# QSPI_Flash_eMMC_uSD-Card.net
KiCad netlist of a schematic drawn in Altium Designer
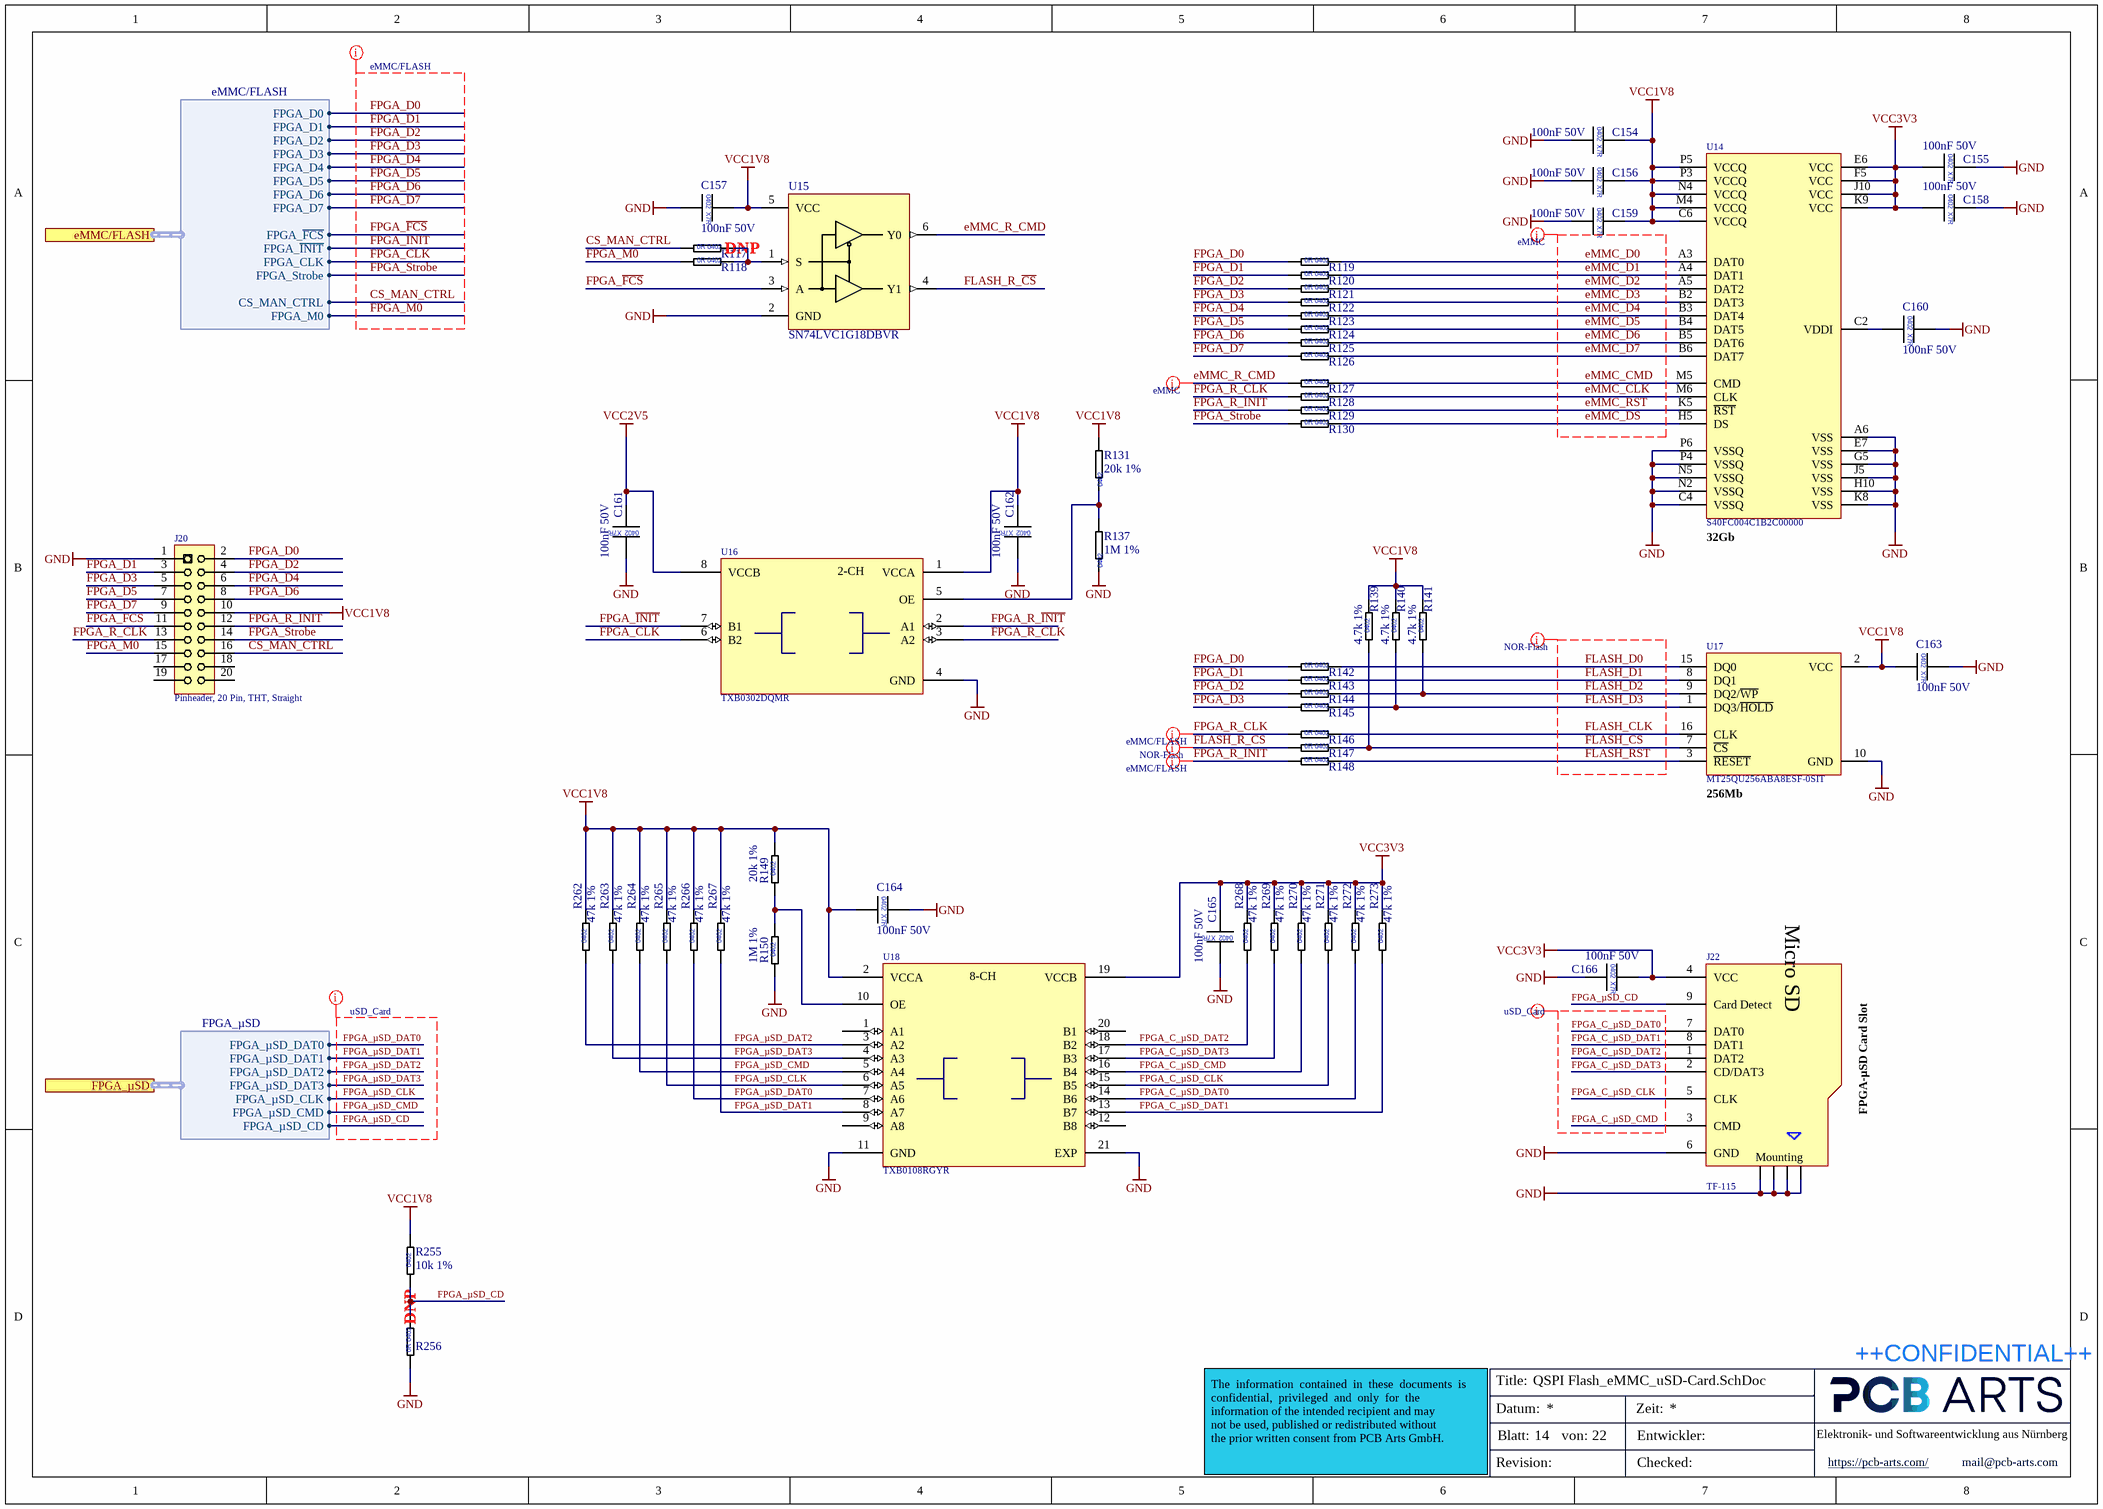
[diagram p0: QSPI Flash_eMMC_uSD-Card.SchDoc]

(export (version "E")
  (design (tool "Eeschema 10.0.6"))
  (components
    (comp (ref "C154")
      (value "100nF 50V")
      (footprint "Cap:CAP_0402_L")
      (description "Multilayer Ceramic Capacitors MLCC - SMD/SMT 0402 50VDC")
      (libsource (lib "Cap") (part "CAP_0402_100nF_50V"))
    )
    (comp (ref "C155")
      (value "100nF 50V")
      (footprint "Cap:CAP_0402_L")
      (description "Multilayer Ceramic Capacitors MLCC - SMD/SMT 0402 50VDC")
      (libsource (lib "Cap") (part "CAP_0402_100nF_50V"))
    )
    (comp (ref "C156")
      (value "100nF 50V")
      (footprint "Cap:CAP_0402_L")
      (description "Multilayer Ceramic Capacitors MLCC - SMD/SMT 0402 50VDC")
      (libsource (lib "Cap") (part "CAP_0402_100nF_50V"))
    )
    (comp (ref "C157")
      (value "100nF 50V")
      (footprint "Cap:CAP_0402_L")
      (description "Multilayer Ceramic Capacitors MLCC - SMD/SMT 0402 50VDC")
      (libsource (lib "Cap") (part "CAP_0402_100nF_50V"))
    )
    (comp (ref "C158")
      (value "100nF 50V")
      (footprint "Cap:CAP_0402_L")
      (description "Multilayer Ceramic Capacitors MLCC - SMD/SMT 0402 50VDC")
      (libsource (lib "Cap") (part "CAP_0402_100nF_50V"))
    )
    (comp (ref "C159")
      (value "100nF 50V")
      (footprint "Cap:CAP_0402_L")
      (description "Multilayer Ceramic Capacitors MLCC - SMD/SMT 0402 50VDC")
      (libsource (lib "Cap") (part "CAP_0402_100nF_50V"))
    )
    (comp (ref "C160")
      (value "100nF 50V")
      (footprint "Cap:CAP_0402_L")
      (description "Multilayer Ceramic Capacitors MLCC - SMD/SMT 0402 50VDC")
      (libsource (lib "Cap") (part "CAP_0402_100nF_50V"))
    )
    (comp (ref "C161")
      (value "100nF 50V")
      (footprint "Cap:CAP_0402_L")
      (description "Multilayer Ceramic Capacitors MLCC - SMD/SMT 0402 50VDC")
      (libsource (lib "") (part "CAP_0402_100nF_50V_1"))
    )
    (comp (ref "C162")
      (value "100nF 50V")
      (footprint "Cap:CAP_0402_L")
      (description "Multilayer Ceramic Capacitors MLCC - SMD/SMT 0402 50VDC")
      (libsource (lib "") (part "CAP_0402_100nF_50V_1"))
    )
    (comp (ref "C163")
      (value "100nF 50V")
      (footprint "Cap:CAP_0402_L")
      (description "Multilayer Ceramic Capacitors MLCC - SMD/SMT 0402 50VDC")
      (libsource (lib "Cap") (part "CAP_0402_100nF_50V"))
    )
    (comp (ref "C164")
      (value "100nF 50V")
      (footprint "Cap:CAP_0402_L")
      (description "Multilayer Ceramic Capacitors MLCC - SMD/SMT 0402 50VDC")
      (libsource (lib "Cap") (part "CAP_0402_100nF_50V"))
    )
    (comp (ref "C165")
      (value "100nF 50V")
      (footprint "Cap:CAP_0402_L")
      (description "Multilayer Ceramic Capacitors MLCC - SMD/SMT 0402 50VDC")
      (libsource (lib "") (part "CAP_0402_100nF_50V_1"))
    )
    (comp (ref "C166")
      (value "100nF 50V")
      (footprint "Cap:CAP_0402_L")
      (description "Multilayer Ceramic Capacitors MLCC - SMD/SMT 0402 50VDC")
      (libsource (lib "Cap") (part "CAP_0402_100nF_50V"))
    )
    (comp (ref "J20")
      (value "Pinheader, 20 Pin, THT, Straight")
      (footprint "Conn:62702021621")
      (description "Box Pin header THT 1.27mm 20Pol Straight")
      (libsource (lib "Conn") (part "62702021621_Box Pin header THT 1.27mm 20Pol Straight"))
    )
    (comp (ref "J22")
      (value "TF-115")
      (footprint "conn:TF-115")
      (description "microSD™ Memory Card 8 connector&Ejector 14.5x14.75x1.85mm Card Sockets Connector")
      (libsource (lib "Conn") (part "TF-115_microSD™ Memory Card 8 connector"))
    )
    (comp (ref "R117")
      (value "0R Jumper")
      (footprint "Res:RES_0402_L")
      (description "Thick Film Resistors - SMD 0Ohm")
      (libsource (lib "Res") (part "RES_0402_0R Jumper"))
    )
    (comp (ref "R118")
      (value "0R Jumper")
      (footprint "Res:RES_0402_L")
      (description "Thick Film Resistors - SMD 0Ohm")
      (libsource (lib "Res") (part "RES_0402_0R Jumper"))
    )
    (comp (ref "R119")
      (value "0R Jumper")
      (footprint "Res:RES_0402_L")
      (description "Thick Film Resistors - SMD 0Ohm")
      (libsource (lib "Res") (part "RES_0402_0R Jumper"))
    )
    (comp (ref "R120")
      (value "0R Jumper")
      (footprint "Res:RES_0402_L")
      (description "Thick Film Resistors - SMD 0Ohm")
      (libsource (lib "Res") (part "RES_0402_0R Jumper"))
    )
    (comp (ref "R121")
      (value "0R Jumper")
      (footprint "Res:RES_0402_L")
      (description "Thick Film Resistors - SMD 0Ohm")
      (libsource (lib "Res") (part "RES_0402_0R Jumper"))
    )
    (comp (ref "R122")
      (value "0R Jumper")
      (footprint "Res:RES_0402_L")
      (description "Thick Film Resistors - SMD 0Ohm")
      (libsource (lib "Res") (part "RES_0402_0R Jumper"))
    )
    (comp (ref "R123")
      (value "0R Jumper")
      (footprint "Res:RES_0402_L")
      (description "Thick Film Resistors - SMD 0Ohm")
      (libsource (lib "Res") (part "RES_0402_0R Jumper"))
    )
    (comp (ref "R124")
      (value "0R Jumper")
      (footprint "Res:RES_0402_L")
      (description "Thick Film Resistors - SMD 0Ohm")
      (libsource (lib "Res") (part "RES_0402_0R Jumper"))
    )
    (comp (ref "R125")
      (value "0R Jumper")
      (footprint "Res:RES_0402_L")
      (description "Thick Film Resistors - SMD 0Ohm")
      (libsource (lib "Res") (part "RES_0402_0R Jumper"))
    )
    (comp (ref "R126")
      (value "0R Jumper")
      (footprint "Res:RES_0402_L")
      (description "Thick Film Resistors - SMD 0Ohm")
      (libsource (lib "Res") (part "RES_0402_0R Jumper"))
    )
    (comp (ref "R127")
      (value "0R Jumper")
      (footprint "Res:RES_0402_L")
      (description "Thick Film Resistors - SMD 0Ohm")
      (libsource (lib "Res") (part "RES_0402_0R Jumper"))
    )
    (comp (ref "R128")
      (value "0R Jumper")
      (footprint "Res:RES_0402_L")
      (description "Thick Film Resistors - SMD 0Ohm")
      (libsource (lib "Res") (part "RES_0402_0R Jumper"))
    )
    (comp (ref "R129")
      (value "0R Jumper")
      (footprint "Res:RES_0402_L")
      (description "Thick Film Resistors - SMD 0Ohm")
      (libsource (lib "Res") (part "RES_0402_0R Jumper"))
    )
    (comp (ref "R130")
      (value "0R Jumper")
      (footprint "Res:RES_0402_L")
      (description "Thick Film Resistors - SMD 0Ohm")
      (libsource (lib "Res") (part "RES_0402_0R Jumper"))
    )
    (comp (ref "R131")
      (value "20k 1%")
      (footprint "Res:RES_0402_L")
      (description "Thick Film Resistors - SMD 20kOhm 1%")
      (libsource (lib "Res") (part "RES_0402_20k_1%"))
    )
    (comp (ref "R137")
      (value "1M 1%")
      (footprint "Res:RES_0402_L")
      (description "Thick Film Resistors - SMD 1MOhm 1%")
      (libsource (lib "Res") (part "RES_0402_1M_1%"))
    )
    (comp (ref "R139")
      (value "4.7k 1%")
      (footprint "Res:RES_0402_L")
      (description "Thick Film Resistors - SMD 4.7kOhm 1%")
      (libsource (lib "Res") (part "RES_0402_4.7k_1%"))
    )
    (comp (ref "R140")
      (value "4.7k 1%")
      (footprint "Res:RES_0402_L")
      (description "Thick Film Resistors - SMD 4.7kOhm 1%")
      (libsource (lib "Res") (part "RES_0402_4.7k_1%"))
    )
    (comp (ref "R141")
      (value "4.7k 1%")
      (footprint "Res:RES_0402_L")
      (description "Thick Film Resistors - SMD 4.7kOhm 1%")
      (libsource (lib "Res") (part "RES_0402_4.7k_1%"))
    )
    (comp (ref "R142")
      (value "0R Jumper")
      (footprint "Res:RES_0402_L")
      (description "Thick Film Resistors - SMD 0Ohm")
      (libsource (lib "Res") (part "RES_0402_0R Jumper"))
    )
    (comp (ref "R143")
      (value "0R Jumper")
      (footprint "Res:RES_0402_L")
      (description "Thick Film Resistors - SMD 0Ohm")
      (libsource (lib "Res") (part "RES_0402_0R Jumper"))
    )
    (comp (ref "R144")
      (value "0R Jumper")
      (footprint "Res:RES_0402_L")
      (description "Thick Film Resistors - SMD 0Ohm")
      (libsource (lib "Res") (part "RES_0402_0R Jumper"))
    )
    (comp (ref "R145")
      (value "0R Jumper")
      (footprint "Res:RES_0402_L")
      (description "Thick Film Resistors - SMD 0Ohm")
      (libsource (lib "Res") (part "RES_0402_0R Jumper"))
    )
    (comp (ref "R146")
      (value "0R Jumper")
      (footprint "Res:RES_0402_L")
      (description "Thick Film Resistors - SMD 0Ohm")
      (libsource (lib "Res") (part "RES_0402_0R Jumper"))
    )
    (comp (ref "R147")
      (value "0R Jumper")
      (footprint "Res:RES_0402_L")
      (description "Thick Film Resistors - SMD 0Ohm")
      (libsource (lib "Res") (part "RES_0402_0R Jumper"))
    )
    (comp (ref "R148")
      (value "0R Jumper")
      (footprint "Res:RES_0402_L")
      (description "Thick Film Resistors - SMD 0Ohm")
      (libsource (lib "Res") (part "RES_0402_0R Jumper"))
    )
    (comp (ref "R149")
      (value "20k 1%")
      (footprint "Res:RES_0402_L")
      (description "Thick Film Resistors - SMD 20kOhm 1%")
      (libsource (lib "Res") (part "RES_0402_20k_1%"))
    )
    (comp (ref "R150")
      (value "1M 1%")
      (footprint "Res:RES_0402_L")
      (description "Thick Film Resistors - SMD 1MOhm 1%")
      (libsource (lib "Res") (part "RES_0402_1M_1%"))
    )
    (comp (ref "R255")
      (value "10k 1%")
      (footprint "Res:RES_0402_L")
      (description "Thick Film Resistors - SMD 10kOhm 1%")
      (libsource (lib "Res") (part "RES_0402_10k_1%"))
    )
    (comp (ref "R256")
      (value "0R Jumper")
      (footprint "res:RES_0402")
      (description "Thick Film Resistors - SMD 0Ohm")
      (libsource (lib "Res") (part "RES_0402_0R Jumper"))
    )
    (comp (ref "R262")
      (value "47k 1%")
      (footprint "Res:RES_0402_L")
      (description "Thick Film Resistors - SMD 47kOhm 1%")
      (libsource (lib "Res") (part "RES_0402_47k_1%"))
    )
    (comp (ref "R263")
      (value "47k 1%")
      (footprint "Res:RES_0402_L")
      (description "Thick Film Resistors - SMD 47kOhm 1%")
      (libsource (lib "Res") (part "RES_0402_47k_1%"))
    )
    (comp (ref "R264")
      (value "47k 1%")
      (footprint "Res:RES_0402_L")
      (description "Thick Film Resistors - SMD 47kOhm 1%")
      (libsource (lib "Res") (part "RES_0402_47k_1%"))
    )
    (comp (ref "R265")
      (value "47k 1%")
      (footprint "Res:RES_0402_L")
      (description "Thick Film Resistors - SMD 47kOhm 1%")
      (libsource (lib "Res") (part "RES_0402_47k_1%"))
    )
    (comp (ref "R266")
      (value "47k 1%")
      (footprint "Res:RES_0402_L")
      (description "Thick Film Resistors - SMD 47kOhm 1%")
      (libsource (lib "Res") (part "RES_0402_47k_1%"))
    )
    (comp (ref "R267")
      (value "47k 1%")
      (footprint "Res:RES_0402_L")
      (description "Thick Film Resistors - SMD 47kOhm 1%")
      (libsource (lib "Res") (part "RES_0402_47k_1%"))
    )
    (comp (ref "R268")
      (value "47k 1%")
      (footprint "Res:RES_0402_L")
      (description "Thick Film Resistors - SMD 47kOhm 1%")
      (libsource (lib "Res") (part "RES_0402_47k_1%"))
    )
    (comp (ref "R269")
      (value "47k 1%")
      (footprint "Res:RES_0402_L")
      (description "Thick Film Resistors - SMD 47kOhm 1%")
      (libsource (lib "Res") (part "RES_0402_47k_1%"))
    )
    (comp (ref "R270")
      (value "47k 1%")
      (footprint "Res:RES_0402_L")
      (description "Thick Film Resistors - SMD 47kOhm 1%")
      (libsource (lib "Res") (part "RES_0402_47k_1%"))
    )
    (comp (ref "R271")
      (value "47k 1%")
      (footprint "Res:RES_0402_L")
      (description "Thick Film Resistors - SMD 47kOhm 1%")
      (libsource (lib "Res") (part "RES_0402_47k_1%"))
    )
    (comp (ref "R272")
      (value "47k 1%")
      (footprint "Res:RES_0402_L")
      (description "Thick Film Resistors - SMD 47kOhm 1%")
      (libsource (lib "Res") (part "RES_0402_47k_1%"))
    )
    (comp (ref "R273")
      (value "47k 1%")
      (footprint "Res:RES_0402_L")
      (description "Thick Film Resistors - SMD 47kOhm 1%")
      (libsource (lib "Res") (part "RES_0402_47k_1%"))
    )
    (comp (ref "U14")
      (value "S40FC004C1B2C00000")
      (footprint "Digital:BGA50P900X750X080-153N")
      (description "eMMC 4GB e.MMC5.1 BGA 9.0 x 7.5 x 0.8 mm")
      (libsource (lib "Digital") (part "S40FC004C1B2C00000_eMMC 4GB e.MMC5.1 BGA 9.0 x 7.5 x 0.8 mm"))
    )
    (comp (ref "U15")
      (value "SN74LVC1G18DBVR")
      (footprint "digital:SOT95P275X110-6N")
      (description "1:2 Noninverting Demultiplexer With 3-State Deselected Output")
      (libsource (lib "Digital") (part "SN74LVC1G18DBVR_1{colon}2 Noninverting Demultiplexer With 3-State Deselected Output"))
    )
    (comp (ref "U16")
      (value "TXB0302DQMR")
      (footprint "Digital:SON40P120X40-8N")
      (description "Translation - Voltage Levels 2B Bidir Vltg-Level Translator")
      (libsource (lib "Digital") (part "TXB0302DQMR_Translation - Voltage Levels 2B Bidir Vltg-Level Translator"))
    )
    (comp (ref "U17")
      (value "MT25QU256ABA8ESF-0SIT")
      (footprint "Digital:SOIC16_Widebody")
      (description "NOR-Flash SPI 256Mbit NOR-Flash /1.8V")
      (libsource (lib "Digital") (part "MT25QU256ABA8ESF-0SIT_NOR-Flash SPI 256Mbit NOR-Flash /1.8V"))
    )
    (comp (ref "U18")
      (value "TXB0108RGYR")
      (footprint "Digital:QFN50P450X350X100-21N")
      (description "Translation - Voltage Levels 8B Bidir Vltg-Level Translator")
      (libsource (lib "Digital") (part "TXB0108RGYR_Translation - Voltage Levels 8B Bidir Vltg-Level Translator"))
    )
  )
  (nets
    (net (code "3") (name "/CS_MAN_CTRL") (class "Default")
      (node (ref "J20") (pin "16") (pinfunction "16_16") (pintype "passive"))
      (node (ref "R117") (pin "1") (pinfunction "1_1") (pintype "passive"))
    )
    (net (code "4") (name "/FLASH_CLK") (class "Default")
      (node (ref "R146") (pin "2") (pinfunction "2_2") (pintype "passive"))
      (node (ref "U17") (pin "16") (pinfunction "CLK_16") (pintype "passive"))
    )
    (net (code "5") (name "/FLASH_D0") (class "Default")
      (node (ref "R142") (pin "2") (pinfunction "2_2") (pintype "passive"))
      (node (ref "U17") (pin "15") (pinfunction "DQ0_15") (pintype "passive"))
    )
    (net (code "6") (name "/FLASH_D1") (class "Default")
      (node (ref "R143") (pin "2") (pinfunction "2_2") (pintype "passive"))
      (node (ref "U17") (pin "8") (pinfunction "DQ1_8") (pintype "passive"))
    )
    (net (code "7") (name "/FLASH_D2") (class "Default")
      (node (ref "R141") (pin "1") (pinfunction "1_1") (pintype "passive"))
      (node (ref "R144") (pin "2") (pinfunction "2_2") (pintype "passive"))
      (node (ref "U17") (pin "9") (pinfunction "DQ2/~{WP}_9") (pintype "passive"))
    )
    (net (code "8") (name "/FLASH_D3") (class "Default")
      (node (ref "R140") (pin "1") (pinfunction "1_1") (pintype "passive"))
      (node (ref "R145") (pin "2") (pinfunction "2_2") (pintype "passive"))
      (node (ref "U17") (pin "1") (pinfunction "DQ3/~{HOLD}_1") (pintype "passive"))
    )
    (net (code "9") (name "/FLASH_R_~{CS}") (class "Default")
      (node (ref "R147") (pin "1") (pinfunction "1_1") (pintype "passive"))
      (node (ref "U15") (pin "4") (pinfunction "Y1_4") (pintype "output"))
    )
    (net (code "10") (name "/FLASH_~{CS}") (class "Default")
      (node (ref "R139") (pin "1") (pinfunction "1_1") (pintype "passive"))
      (node (ref "R147") (pin "2") (pinfunction "2_2") (pintype "passive"))
      (node (ref "U17") (pin "7") (pinfunction "~{CS}_7") (pintype "passive"))
    )
    (net (code "11") (name "/FLASH_~{RST}") (class "Default")
      (node (ref "R148") (pin "2") (pinfunction "2_2") (pintype "passive"))
      (node (ref "U17") (pin "3") (pinfunction "~{RESET}_3") (pintype "passive"))
    )
    (net (code "12") (name "/FPGA_CLK") (class "Default")
      (node (ref "U16") (pin "6") (pinfunction "B2_6") (pintype "bidirectional"))
    )
    (net (code "13") (name "/FPGA_C_µSD_CLK") (class "Default")
      (node (ref "J22") (pin "5") (pinfunction "CLK_5") (pintype "passive"))
      (node (ref "R271") (pin "1") (pinfunction "1_1") (pintype "passive"))
      (node (ref "U18") (pin "15") (pinfunction "B5_15") (pintype "bidirectional"))
    )
    (net (code "14") (name "/FPGA_C_µSD_CMD") (class "Default")
      (node (ref "J22") (pin "3") (pinfunction "CMD_3") (pintype "passive"))
      (node (ref "R270") (pin "1") (pinfunction "1_1") (pintype "passive"))
      (node (ref "U18") (pin "16") (pinfunction "B4_16") (pintype "bidirectional"))
    )
    (net (code "15") (name "/FPGA_C_µSD_DAT0") (class "Default")
      (node (ref "J22") (pin "7") (pinfunction "DAT0_7") (pintype "passive"))
      (node (ref "R272") (pin "1") (pinfunction "1_1") (pintype "passive"))
      (node (ref "U18") (pin "14") (pinfunction "B6_14") (pintype "bidirectional"))
    )
    (net (code "16") (name "/FPGA_C_µSD_DAT1") (class "Default")
      (node (ref "J22") (pin "8") (pinfunction "DAT1_8") (pintype "passive"))
      (node (ref "R273") (pin "1") (pinfunction "1_1") (pintype "passive"))
      (node (ref "U18") (pin "13") (pinfunction "B7_13") (pintype "bidirectional"))
    )
    (net (code "17") (name "/FPGA_C_µSD_DAT2") (class "Default")
      (node (ref "J22") (pin "1") (pinfunction "DAT2_1") (pintype "passive"))
      (node (ref "R268") (pin "1") (pinfunction "1_1") (pintype "passive"))
      (node (ref "U18") (pin "18") (pinfunction "B2_18") (pintype "bidirectional"))
    )
    (net (code "18") (name "/FPGA_C_µSD_DAT3") (class "Default")
      (node (ref "J22") (pin "2") (pinfunction "CD/DAT3_2") (pintype "passive"))
      (node (ref "R269") (pin "1") (pinfunction "1_1") (pintype "passive"))
      (node (ref "U18") (pin "17") (pinfunction "B3_17") (pintype "bidirectional"))
    )
    (net (code "19") (name "/FPGA_D0") (class "Default")
      (node (ref "J20") (pin "2") (pinfunction "2_2") (pintype "passive"))
      (node (ref "R119") (pin "1") (pinfunction "1_1") (pintype "passive"))
      (node (ref "R142") (pin "1") (pinfunction "1_1") (pintype "passive"))
    )
    (net (code "20") (name "/FPGA_D1") (class "Default")
      (node (ref "J20") (pin "3") (pinfunction "3_3") (pintype "passive"))
      (node (ref "R120") (pin "1") (pinfunction "1_1") (pintype "passive"))
      (node (ref "R143") (pin "1") (pinfunction "1_1") (pintype "passive"))
    )
    (net (code "21") (name "/FPGA_D2") (class "Default")
      (node (ref "J20") (pin "4") (pinfunction "4_4") (pintype "passive"))
      (node (ref "R121") (pin "1") (pinfunction "1_1") (pintype "passive"))
      (node (ref "R144") (pin "1") (pinfunction "1_1") (pintype "passive"))
    )
    (net (code "22") (name "/FPGA_D3") (class "Default")
      (node (ref "J20") (pin "5") (pinfunction "5_5") (pintype "passive"))
      (node (ref "R122") (pin "1") (pinfunction "1_1") (pintype "passive"))
      (node (ref "R145") (pin "1") (pinfunction "1_1") (pintype "passive"))
    )
    (net (code "23") (name "/FPGA_D4") (class "Default")
      (node (ref "J20") (pin "6") (pinfunction "6_6") (pintype "passive"))
      (node (ref "R123") (pin "1") (pinfunction "1_1") (pintype "passive"))
    )
    (net (code "24") (name "/FPGA_D5") (class "Default")
      (node (ref "J20") (pin "7") (pinfunction "7_7") (pintype "passive"))
      (node (ref "R124") (pin "1") (pinfunction "1_1") (pintype "passive"))
    )
    (net (code "25") (name "/FPGA_D6") (class "Default")
      (node (ref "J20") (pin "8") (pinfunction "8_8") (pintype "passive"))
      (node (ref "R125") (pin "1") (pinfunction "1_1") (pintype "passive"))
    )
    (net (code "26") (name "/FPGA_D7") (class "Default")
      (node (ref "J20") (pin "9") (pinfunction "9_9") (pintype "passive"))
      (node (ref "R126") (pin "1") (pinfunction "1_1") (pintype "passive"))
    )
    (net (code "27") (name "/FPGA_M0") (class "Default")
      (node (ref "J20") (pin "15") (pinfunction "15_15") (pintype "passive"))
      (node (ref "R118") (pin "1") (pinfunction "1_1") (pintype "passive"))
    )
    (net (code "28") (name "/FPGA_R_CLK") (class "Default")
      (node (ref "J20") (pin "13") (pinfunction "13_13") (pintype "passive"))
      (node (ref "R128") (pin "1") (pinfunction "1_1") (pintype "passive"))
      (node (ref "R146") (pin "1") (pinfunction "1_1") (pintype "passive"))
      (node (ref "U16") (pin "3") (pinfunction "A2_3") (pintype "bidirectional"))
    )
    (net (code "29") (name "/FPGA_R_~{INIT}") (class "Default")
      (node (ref "J20") (pin "12") (pinfunction "12_12") (pintype "passive"))
      (node (ref "R129") (pin "1") (pinfunction "1_1") (pintype "passive"))
      (node (ref "R148") (pin "1") (pinfunction "1_1") (pintype "passive"))
      (node (ref "U16") (pin "2") (pinfunction "A1_2") (pintype "bidirectional"))
    )
    (net (code "30") (name "/FPGA_Strobe") (class "Default")
      (node (ref "J20") (pin "14") (pinfunction "14_14") (pintype "passive"))
      (node (ref "R130") (pin "1") (pinfunction "1_1") (pintype "passive"))
    )
    (net (code "31") (name "/FPGA_~{FCS}") (class "Default")
      (node (ref "J20") (pin "11") (pinfunction "11_11") (pintype "passive"))
      (node (ref "U15") (pin "3") (pinfunction "A_3") (pintype "input"))
    )
    (net (code "32") (name "/FPGA_~{INIT}") (class "Default")
      (node (ref "U16") (pin "7") (pinfunction "B1_7") (pintype "bidirectional"))
    )
    (net (code "33") (name "/FPGA_µSD_CD") (class "Default")
      (node (ref "J22") (pin "9") (pinfunction "Card_Detect_9") (pintype "passive"))
      (node (ref "R255") (pin "1") (pinfunction "1_1") (pintype "passive"))
      (node (ref "R256") (pin "2") (pinfunction "2_2") (pintype "passive"))
    )
    (net (code "34") (name "/FPGA_µSD_CLK") (class "Default")
      (node (ref "R265") (pin "1") (pinfunction "1_1") (pintype "passive"))
      (node (ref "U18") (pin "6") (pinfunction "A5_6") (pintype "bidirectional"))
    )
    (net (code "35") (name "/FPGA_µSD_CMD") (class "Default")
      (node (ref "R264") (pin "1") (pinfunction "1_1") (pintype "passive"))
      (node (ref "U18") (pin "5") (pinfunction "A4_5") (pintype "bidirectional"))
    )
    (net (code "36") (name "/FPGA_µSD_DAT0") (class "Default")
      (node (ref "R266") (pin "1") (pinfunction "1_1") (pintype "passive"))
      (node (ref "U18") (pin "7") (pinfunction "A6_7") (pintype "bidirectional"))
    )
    (net (code "37") (name "/FPGA_µSD_DAT1") (class "Default")
      (node (ref "R267") (pin "1") (pinfunction "1_1") (pintype "passive"))
      (node (ref "U18") (pin "8") (pinfunction "A7_8") (pintype "bidirectional"))
    )
    (net (code "38") (name "/FPGA_µSD_DAT2") (class "Default")
      (node (ref "R262") (pin "1") (pinfunction "1_1") (pintype "passive"))
      (node (ref "U18") (pin "3") (pinfunction "A2_3") (pintype "bidirectional"))
    )
    (net (code "39") (name "/FPGA_µSD_DAT3") (class "Default")
      (node (ref "R263") (pin "1") (pinfunction "1_1") (pintype "passive"))
      (node (ref "U18") (pin "4") (pinfunction "A3_4") (pintype "bidirectional"))
    )
    (net (code "40") (name "/eMMC_CLK") (class "Default")
      (node (ref "R128") (pin "2") (pinfunction "2_2") (pintype "passive"))
      (node (ref "U14") (pin "M6") (pinfunction "CLK_M6") (pintype "passive"))
    )
    (net (code "41") (name "/eMMC_CMD") (class "Default")
      (node (ref "R127") (pin "2") (pinfunction "2_2") (pintype "passive"))
      (node (ref "U14") (pin "M5") (pinfunction "CMD_M5") (pintype "passive"))
    )
    (net (code "42") (name "/eMMC_D0") (class "Default")
      (node (ref "R119") (pin "2") (pinfunction "2_2") (pintype "passive"))
      (node (ref "U14") (pin "A3") (pinfunction "DAT0_A3") (pintype "passive"))
    )
    (net (code "43") (name "/eMMC_D1") (class "Default")
      (node (ref "R120") (pin "2") (pinfunction "2_2") (pintype "passive"))
      (node (ref "U14") (pin "A4") (pinfunction "DAT1_A4") (pintype "passive"))
    )
    (net (code "44") (name "/eMMC_D2") (class "Default")
      (node (ref "R121") (pin "2") (pinfunction "2_2") (pintype "passive"))
      (node (ref "U14") (pin "A5") (pinfunction "DAT2_A5") (pintype "passive"))
    )
    (net (code "45") (name "/eMMC_D3") (class "Default")
      (node (ref "R122") (pin "2") (pinfunction "2_2") (pintype "passive"))
      (node (ref "U14") (pin "B2") (pinfunction "DAT3_B2") (pintype "passive"))
    )
    (net (code "46") (name "/eMMC_D4") (class "Default")
      (node (ref "R123") (pin "2") (pinfunction "2_2") (pintype "passive"))
      (node (ref "U14") (pin "B3") (pinfunction "DAT4_B3") (pintype "passive"))
    )
    (net (code "47") (name "/eMMC_D5") (class "Default")
      (node (ref "R124") (pin "2") (pinfunction "2_2") (pintype "passive"))
      (node (ref "U14") (pin "B4") (pinfunction "DAT5_B4") (pintype "passive"))
    )
    (net (code "48") (name "/eMMC_D6") (class "Default")
      (node (ref "R125") (pin "2") (pinfunction "2_2") (pintype "passive"))
      (node (ref "U14") (pin "B5") (pinfunction "DAT6_B5") (pintype "passive"))
    )
    (net (code "49") (name "/eMMC_D7") (class "Default")
      (node (ref "R126") (pin "2") (pinfunction "2_2") (pintype "passive"))
      (node (ref "U14") (pin "B6") (pinfunction "DAT7_B6") (pintype "passive"))
    )
    (net (code "50") (name "/eMMC_DS") (class "Default")
      (node (ref "R130") (pin "2") (pinfunction "2_2") (pintype "passive"))
      (node (ref "U14") (pin "H5") (pinfunction "DS_H5") (pintype "passive"))
    )
    (net (code "51") (name "/eMMC_R_CMD") (class "Default")
      (node (ref "R127") (pin "1") (pinfunction "1_1") (pintype "passive"))
      (node (ref "U15") (pin "6") (pinfunction "Y0_6") (pintype "output"))
    )
    (net (code "52") (name "/eMMC_~{RST}") (class "Default")
      (node (ref "R129") (pin "2") (pinfunction "2_2") (pintype "passive"))
      (node (ref "U14") (pin "K5") (pinfunction "~{RST}_K5") (pintype "passive"))
    )
    (net (code "55") (name "GND") (class "Default")
      (node (ref "C154") (pin "2") (pinfunction "2_2") (pintype "passive"))
      (node (ref "C155") (pin "1") (pinfunction "1_1") (pintype "passive"))
      (node (ref "C156") (pin "2") (pinfunction "2_2") (pintype "passive"))
      (node (ref "C157") (pin "2") (pinfunction "2_2") (pintype "passive"))
      (node (ref "C158") (pin "1") (pinfunction "1_1") (pintype "passive"))
      (node (ref "C159") (pin "2") (pinfunction "2_2") (pintype "passive"))
      (node (ref "C160") (pin "1") (pinfunction "1_1") (pintype "passive"))
      (node (ref "C161") (pin "1") (pinfunction "1_1") (pintype "passive"))
      (node (ref "C162") (pin "1") (pinfunction "1_1") (pintype "passive"))
      (node (ref "C163") (pin "1") (pinfunction "1_1") (pintype "passive"))
      (node (ref "C164") (pin "1") (pinfunction "1_1") (pintype "passive"))
      (node (ref "C165") (pin "1") (pinfunction "1_1") (pintype "passive"))
      (node (ref "C166") (pin "2") (pinfunction "2_2") (pintype "passive"))
      (node (ref "J20") (pin "1") (pinfunction "1_1") (pintype "passive"))
      (node (ref "J22") (pin "10") (pinfunction "10_10") (pintype "passive"))
      (node (ref "J22") (pin "11") (pinfunction "11_11") (pintype "passive"))
      (node (ref "J22") (pin "12") (pinfunction "12_12") (pintype "passive"))
      (node (ref "J22") (pin "13") (pinfunction "13_13") (pintype "passive"))
      (node (ref "J22") (pin "6") (pinfunction "GND_6") (pintype "passive"))
      (node (ref "R137") (pin "1") (pinfunction "1_1") (pintype "passive"))
      (node (ref "R150") (pin "1") (pinfunction "1_1") (pintype "passive"))
      (node (ref "R256") (pin "1") (pinfunction "1_1") (pintype "passive"))
      (node (ref "U14") (pin "A6") (pinfunction "VSS_A6") (pintype "passive"))
      (node (ref "U14") (pin "C4") (pinfunction "VSSQ_C4") (pintype "passive"))
      (node (ref "U14") (pin "E7") (pinfunction "VSS_E7") (pintype "passive"))
      (node (ref "U14") (pin "G5") (pinfunction "VSS_G5") (pintype "passive"))
      (node (ref "U14") (pin "H10") (pinfunction "VSS_H10") (pintype "passive"))
      (node (ref "U14") (pin "J5") (pinfunction "VSS_J5") (pintype "passive"))
      (node (ref "U14") (pin "K8") (pinfunction "VSS_K8") (pintype "passive"))
      (node (ref "U14") (pin "N2") (pinfunction "VSSQ_N2") (pintype "passive"))
      (node (ref "U14") (pin "N5") (pinfunction "VSSQ_N5") (pintype "passive"))
      (node (ref "U14") (pin "P4") (pinfunction "VSSQ_P4") (pintype "passive"))
      (node (ref "U14") (pin "P6") (pinfunction "VSSQ_P6") (pintype "passive"))
      (node (ref "U15") (pin "2") (pinfunction "GND_2") (pintype "power_in"))
      (node (ref "U16") (pin "4") (pinfunction "GND_4") (pintype "power_in"))
      (node (ref "U17") (pin "10") (pinfunction "GND_10") (pintype "passive"))
      (node (ref "U18") (pin "11") (pinfunction "GND_11") (pintype "power_in"))
      (node (ref "U18") (pin "21") (pinfunction "EXP_21") (pintype "power_in"))
    )
    (net (code "56") (name "Net-(U14-VDDI)") (class "Default")
      (node (ref "C160") (pin "2") (pinfunction "2_2") (pintype "passive"))
      (node (ref "U14") (pin "C2") (pinfunction "VDDI_C2") (pintype "passive"))
    )
    (net (code "57") (name "Net-(U15-S)") (class "Default")
      (node (ref "R117") (pin "2") (pinfunction "2_2") (pintype "passive"))
      (node (ref "R118") (pin "2") (pinfunction "2_2") (pintype "passive"))
      (node (ref "U15") (pin "1") (pinfunction "S_1") (pintype "input"))
    )
    (net (code "58") (name "Net-(U16-OE)") (class "Default")
      (node (ref "R131") (pin "1") (pinfunction "1_1") (pintype "passive"))
      (node (ref "R137") (pin "2") (pinfunction "2_2") (pintype "passive"))
      (node (ref "U16") (pin "5") (pinfunction "OE_5") (pintype "power_in"))
    )
    (net (code "59") (name "Net-(U18-OE)") (class "Default")
      (node (ref "R149") (pin "1") (pinfunction "1_1") (pintype "passive"))
      (node (ref "R150") (pin "2") (pinfunction "2_2") (pintype "passive"))
      (node (ref "U18") (pin "10") (pinfunction "OE_10") (pintype "power_in"))
    )
    (net (code "60") (name "VCC1V8") (class "Default")
      (node (ref "C154") (pin "1") (pinfunction "1_1") (pintype "passive"))
      (node (ref "C156") (pin "1") (pinfunction "1_1") (pintype "passive"))
      (node (ref "C157") (pin "1") (pinfunction "1_1") (pintype "passive"))
      (node (ref "C159") (pin "1") (pinfunction "1_1") (pintype "passive"))
      (node (ref "C162") (pin "2") (pinfunction "2_2") (pintype "passive"))
      (node (ref "C163") (pin "2") (pinfunction "2_2") (pintype "passive"))
      (node (ref "C164") (pin "2") (pinfunction "2_2") (pintype "passive"))
      (node (ref "J20") (pin "10") (pinfunction "10_10") (pintype "passive"))
      (node (ref "R131") (pin "2") (pinfunction "2_2") (pintype "passive"))
      (node (ref "R139") (pin "2") (pinfunction "2_2") (pintype "passive"))
      (node (ref "R140") (pin "2") (pinfunction "2_2") (pintype "passive"))
      (node (ref "R141") (pin "2") (pinfunction "2_2") (pintype "passive"))
      (node (ref "R149") (pin "2") (pinfunction "2_2") (pintype "passive"))
      (node (ref "R255") (pin "2") (pinfunction "2_2") (pintype "passive"))
      (node (ref "R262") (pin "2") (pinfunction "2_2") (pintype "passive"))
      (node (ref "R263") (pin "2") (pinfunction "2_2") (pintype "passive"))
      (node (ref "R264") (pin "2") (pinfunction "2_2") (pintype "passive"))
      (node (ref "R265") (pin "2") (pinfunction "2_2") (pintype "passive"))
      (node (ref "R266") (pin "2") (pinfunction "2_2") (pintype "passive"))
      (node (ref "R267") (pin "2") (pinfunction "2_2") (pintype "passive"))
      (node (ref "U14") (pin "C6") (pinfunction "VCCQ_C6") (pintype "passive"))
      (node (ref "U14") (pin "M4") (pinfunction "VCCQ_M4") (pintype "passive"))
      (node (ref "U14") (pin "N4") (pinfunction "VCCQ_N4") (pintype "passive"))
      (node (ref "U14") (pin "P3") (pinfunction "VCCQ_P3") (pintype "passive"))
      (node (ref "U14") (pin "P5") (pinfunction "VCCQ_P5") (pintype "passive"))
      (node (ref "U15") (pin "5") (pinfunction "VCC_5") (pintype "power_in"))
      (node (ref "U16") (pin "1") (pinfunction "VCCA_1") (pintype "power_in"))
      (node (ref "U17") (pin "2") (pinfunction "VCC_2") (pintype "passive"))
      (node (ref "U18") (pin "2") (pinfunction "VCCA_2") (pintype "power_in"))
    )
    (net (code "61") (name "VCC2V5") (class "Default")
      (node (ref "C161") (pin "2") (pinfunction "2_2") (pintype "passive"))
      (node (ref "U16") (pin "8") (pinfunction "VCCB_8") (pintype "power_in"))
    )
    (net (code "62") (name "VCC3V3") (class "Default")
      (node (ref "C155") (pin "2") (pinfunction "2_2") (pintype "passive"))
      (node (ref "C158") (pin "2") (pinfunction "2_2") (pintype "passive"))
      (node (ref "C165") (pin "2") (pinfunction "2_2") (pintype "passive"))
      (node (ref "C166") (pin "1") (pinfunction "1_1") (pintype "passive"))
      (node (ref "J22") (pin "4") (pinfunction "VCC_4") (pintype "passive"))
      (node (ref "R268") (pin "2") (pinfunction "2_2") (pintype "passive"))
      (node (ref "R269") (pin "2") (pinfunction "2_2") (pintype "passive"))
      (node (ref "R270") (pin "2") (pinfunction "2_2") (pintype "passive"))
      (node (ref "R271") (pin "2") (pinfunction "2_2") (pintype "passive"))
      (node (ref "R272") (pin "2") (pinfunction "2_2") (pintype "passive"))
      (node (ref "R273") (pin "2") (pinfunction "2_2") (pintype "passive"))
      (node (ref "U14") (pin "E6") (pinfunction "VCC_E6") (pintype "passive"))
      (node (ref "U14") (pin "F5") (pinfunction "VCC_F5") (pintype "passive"))
      (node (ref "U14") (pin "J10") (pinfunction "VCC_J10") (pintype "passive"))
      (node (ref "U14") (pin "K9") (pinfunction "VCC_K9") (pintype "passive"))
      (node (ref "U18") (pin "19") (pinfunction "VCCB_19") (pintype "power_in"))
    )
    (net (code "63") (name "unconnected-(J20-Pad17)") (class "Default")
      (node (ref "J20") (pin "17") (pinfunction "17_17") (pintype "passive"))
    )
    (net (code "64") (name "unconnected-(J20-Pad18)") (class "Default")
      (node (ref "J20") (pin "18") (pinfunction "18_18") (pintype "passive"))
    )
    (net (code "65") (name "unconnected-(J20-Pad19)") (class "Default")
      (node (ref "J20") (pin "19") (pinfunction "19_19") (pintype "passive"))
    )
    (net (code "66") (name "unconnected-(J20-Pad20)") (class "Default")
      (node (ref "J20") (pin "20") (pinfunction "20_20") (pintype "passive"))
    )
    (net (code "67") (name "unconnected-(U18-A1-Pad1)") (class "Default")
      (node (ref "U18") (pin "1") (pinfunction "A1_1") (pintype "bidirectional"))
    )
    (net (code "68") (name "unconnected-(U18-A8-Pad9)") (class "Default")
      (node (ref "U18") (pin "9") (pinfunction "A8_9") (pintype "bidirectional"))
    )
    (net (code "69") (name "unconnected-(U18-B1-Pad20)") (class "Default")
      (node (ref "U18") (pin "20") (pinfunction "B1_20") (pintype "bidirectional"))
    )
    (net (code "70") (name "unconnected-(U18-B8-Pad12)") (class "Default")
      (node (ref "U18") (pin "12") (pinfunction "B8_12") (pintype "bidirectional"))
    )
  )
)
